# Programiralica.net
KiCad netlist of a schematic drawn in Altium Designer
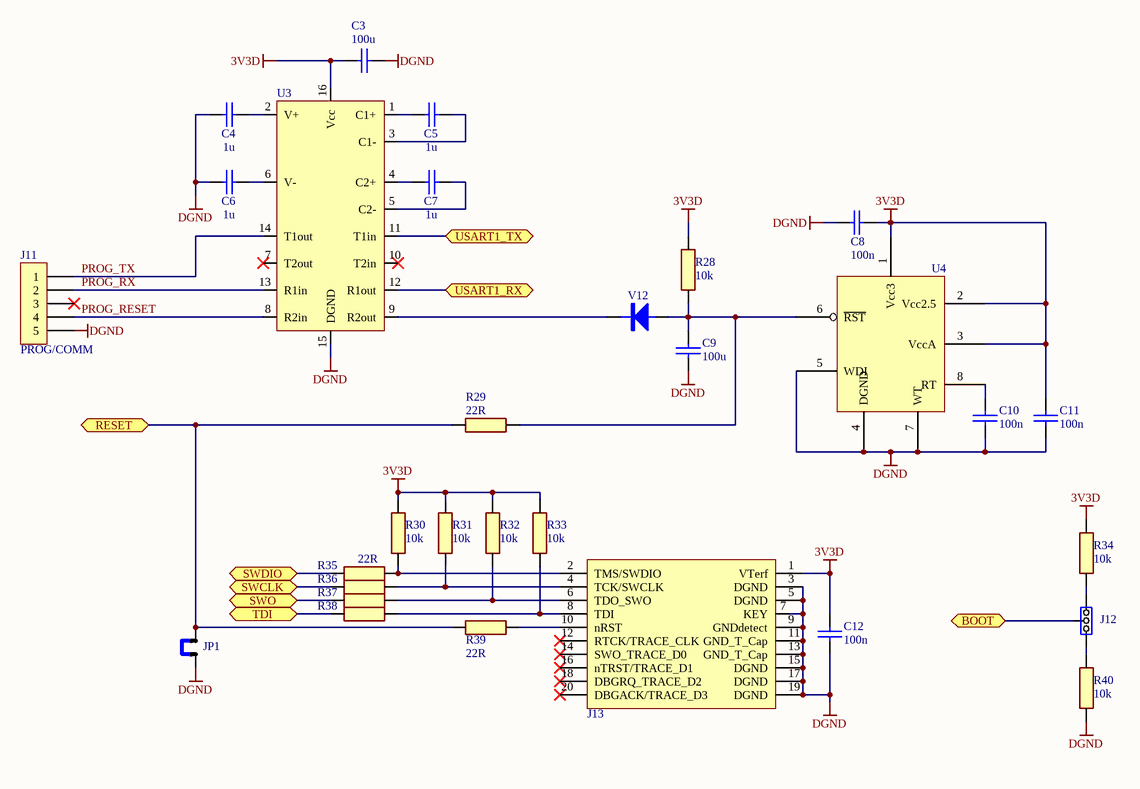
[diagram p0: Programiralica.SchDoc]

(export (version "E")
  (design (tool "Eeschema 10.0.6"))
  (components
    (comp (ref "C3")
      (value "100u")
      (footprint "CAP_0805_SMD")
      (description "0805")
      (libsource (lib "Moj_lib") (part "CAP"))
    )
    (comp (ref "C4")
      (value "1u")
      (footprint "CAP_0805_SMD")
      (description "0805")
      (libsource (lib "Moj_lib") (part "CAP"))
    )
    (comp (ref "C5")
      (value "1u")
      (footprint "CAP_0805_SMD")
      (description "0805")
      (libsource (lib "Moj_lib") (part "CAP"))
    )
    (comp (ref "C6")
      (value "1u")
      (footprint "CAP_0805_SMD")
      (description "0805")
      (libsource (lib "Moj_lib") (part "CAP"))
    )
    (comp (ref "C7")
      (value "1u")
      (footprint "CAP_0805_SMD")
      (description "0805")
      (libsource (lib "Moj_lib") (part "CAP"))
    )
    (comp (ref "C8")
      (value "100n")
      (footprint "CAP_0805_SMD")
      (description "0805")
      (libsource (lib "Moj_lib") (part "CAP"))
    )
    (comp (ref "C9")
      (value "100u")
      (footprint "CAP_0805_SMD")
      (description "0805")
      (libsource (lib "Moj_lib") (part "CAP"))
    )
    (comp (ref "C10")
      (value "100n")
      (footprint "CAP_0805_SMD")
      (description "0805")
      (libsource (lib "Moj_lib") (part "CAP"))
    )
    (comp (ref "C11")
      (value "100n")
      (footprint "CAP_0805_SMD")
      (description "0805")
      (libsource (lib "Moj_lib") (part "CAP"))
    )
    (comp (ref "C12")
      (value "100n")
      (footprint "CAP_0805_SMD")
      (description "0805")
      (libsource (lib "Moj_lib") (part "CAP"))
    )
    (comp (ref "J11")
      (value "PROG/COMM")
      (footprint "CON-SIP-5")
      (description "5 Pin connector")
      (libsource (lib "Moj_lib") (part "CON5"))
    )
    (comp (ref "J12")
      (value "JUMPER_3_POLE")
      (footprint "JUMPER_3_POLE")
      (description "3 Pole jumper")
      (libsource (lib "Moj_lib") (part "JUMPER_3_POLE"))
    )
    (comp (ref "J13")
      (value "JTAG-DEBUG-10x2")
      (footprint "JTAG-DEBUG-10x2-MOJ")
      (libsource (lib "Moj_lib") (part "CON-JTAG-10x2"))
    )
    (comp (ref "JP1")
      (value "JUMPER")
      (footprint "KRATKO-LEMNI")
      (description "Jumper")
      (libsource (lib "ShemaLibrary_IEL") (part "JUMPER"))
    )
    (comp (ref "R28")
      (value "10k")
      (footprint "RES_0805_SMD")
      (description "0805")
      (libsource (lib "") (part "RES_1"))
    )
    (comp (ref "R29")
      (value "22R")
      (footprint "RES_0805_SMD")
      (description "0805")
      (libsource (lib "") (part "RES_1"))
    )
    (comp (ref "R30")
      (value "10k")
      (footprint "RES_0805_SMD")
      (description "0805")
      (libsource (lib "Moj_lib") (part "RES"))
    )
    (comp (ref "R31")
      (value "10k")
      (footprint "RES_0805_SMD")
      (description "0805")
      (libsource (lib "Moj_lib") (part "RES"))
    )
    (comp (ref "R32")
      (value "10k")
      (footprint "RES_0805_SMD")
      (description "0805")
      (libsource (lib "Moj_lib") (part "RES"))
    )
    (comp (ref "R33")
      (value "10k")
      (footprint "RES_0805_SMD")
      (description "0805")
      (libsource (lib "Moj_lib") (part "RES"))
    )
    (comp (ref "R34")
      (value "10k")
      (footprint "RES_0805_SMD")
      (description "0805")
      (libsource (lib "Moj_lib") (part "RES"))
    )
    (comp (ref "R35")
      (value "22R")
      (footprint "RES_0805_SMD")
      (description "0805")
      (libsource (lib "") (part "RES_1"))
    )
    (comp (ref "R36")
      (value "22R")
      (footprint "RES_0805_SMD")
      (description "0805")
      (libsource (lib "") (part "RES_1"))
    )
    (comp (ref "R37")
      (value "22R")
      (footprint "RES_0805_SMD")
      (description "0805")
      (libsource (lib "") (part "RES_1"))
    )
    (comp (ref "R38")
      (value "22R")
      (footprint "RES_0805_SMD")
      (description "0805")
      (libsource (lib "") (part "RES_1"))
    )
    (comp (ref "R39")
      (value "22R")
      (footprint "RES_0805_SMD")
      (description "0805")
      (libsource (lib "") (part "RES_1"))
    )
    (comp (ref "R40")
      (value "10k")
      (footprint "RES_0805_SMD")
      (description "0805")
      (libsource (lib "Moj_lib") (part "RES"))
    )
    (comp (ref "U3")
      (value "MAX3232")
      (footprint "MAX3232")
      (description "RS232 chip")
      (libsource (lib "Moj_lib") (part "MAX3232"))
    )
    (comp (ref "U4") (value "LTC1726") (footprint "LTC1726") (libsource (lib "Moj_lib") (part "LTC1726")))
    (comp (ref "V12")
      (value "DIODE")
      (footprint "SOD-323F")
      (description "SMD diode")
      (libsource (lib "ShemaLibrary_IEL") (part "DIODE"))
    )
  )
  (nets
    (net (code "1") (name "/BOOT") (class "Default") (node (ref "J12") (pin "2") (pintype "passive")))
    (net (code "2") (name "/PROG_RESET") (class "Default")
      (node (ref "J11") (pin "4") (pinfunction "4_4") (pintype "passive"))
      (node (ref "U3") (pin "8") (pinfunction "R2in_8") (pintype "passive"))
    )
    (net (code "3") (name "/PROG_RX") (class "Default")
      (node (ref "J11") (pin "2") (pinfunction "2_2") (pintype "passive"))
      (node (ref "U3") (pin "13") (pinfunction "R1in_13") (pintype "passive"))
    )
    (net (code "4") (name "/PROG_TX") (class "Default")
      (node (ref "J11") (pin "1") (pinfunction "1_1") (pintype "passive"))
      (node (ref "U3") (pin "14") (pinfunction "T1out_14") (pintype "passive"))
    )
    (net (code "5") (name "/RESET") (class "Default")
      (node (ref "JP1") (pin "2") (pintype "passive"))
      (node (ref "R29") (pin "1") (pinfunction "1_1") (pintype "passive"))
      (node (ref "R39") (pin "1") (pinfunction "1_1") (pintype "passive"))
    )
    (net (code "6") (name "/SWCLK") (class "Default")
      (node (ref "R36") (pin "1") (pinfunction "1_1") (pintype "passive"))
    )
    (net (code "7") (name "/SWDIO") (class "Default")
      (node (ref "R35") (pin "1") (pinfunction "1_1") (pintype "passive"))
    )
    (net (code "8") (name "/SWO") (class "Default")
      (node (ref "R37") (pin "1") (pinfunction "1_1") (pintype "passive"))
    )
    (net (code "9") (name "/TDI") (class "Default")
      (node (ref "R38") (pin "1") (pinfunction "1_1") (pintype "passive"))
    )
    (net (code "10") (name "/USART1_RX") (class "Default")
      (node (ref "U3") (pin "12") (pinfunction "R1out_12") (pintype "passive"))
    )
    (net (code "11") (name "/USART1_TX") (class "Default")
      (node (ref "U3") (pin "11") (pinfunction "T1in_11") (pintype "passive"))
    )
    (net (code "12") (name "3V3D") (class "Default")
      (node (ref "C11") (pin "2") (pinfunction "2_2") (pintype "passive"))
      (node (ref "C12") (pin "2") (pinfunction "2_2") (pintype "passive"))
      (node (ref "C3") (pin "1") (pinfunction "1_1") (pintype "passive"))
      (node (ref "C8") (pin "1") (pinfunction "1_1") (pintype "passive"))
      (node (ref "J13") (pin "1") (pinfunction "VTerf_1") (pintype "passive"))
      (node (ref "R28") (pin "2") (pinfunction "2_2") (pintype "passive"))
      (node (ref "R30") (pin "2") (pinfunction "2_2") (pintype "passive"))
      (node (ref "R31") (pin "2") (pinfunction "2_2") (pintype "passive"))
      (node (ref "R32") (pin "2") (pinfunction "2_2") (pintype "passive"))
      (node (ref "R33") (pin "2") (pinfunction "2_2") (pintype "passive"))
      (node (ref "R34") (pin "2") (pinfunction "2_2") (pintype "passive"))
      (node (ref "U3") (pin "16") (pinfunction "Vcc_16") (pintype "passive"))
      (node (ref "U4") (pin "1") (pinfunction "Vcc3_1") (pintype "passive"))
      (node (ref "U4") (pin "2") (pinfunction "Vcc2.5_2") (pintype "passive"))
      (node (ref "U4") (pin "3") (pinfunction "VccA_3") (pintype "passive"))
    )
    (net (code "13") (name "DGND") (class "Default")
      (node (ref "C10") (pin "1") (pinfunction "1_1") (pintype "passive"))
      (node (ref "C11") (pin "1") (pinfunction "1_1") (pintype "passive"))
      (node (ref "C12") (pin "1") (pinfunction "1_1") (pintype "passive"))
      (node (ref "C3") (pin "2") (pinfunction "2_2") (pintype "passive"))
      (node (ref "C4") (pin "1") (pinfunction "1_1") (pintype "passive"))
      (node (ref "C6") (pin "1") (pinfunction "1_1") (pintype "passive"))
      (node (ref "C8") (pin "2") (pinfunction "2_2") (pintype "passive"))
      (node (ref "C9") (pin "1") (pinfunction "1_1") (pintype "passive"))
      (node (ref "J11") (pin "5") (pinfunction "5_5") (pintype "passive"))
      (node (ref "J13") (pin "11") (pinfunction "GND_T_Cap_11") (pintype "passive"))
      (node (ref "J13") (pin "13") (pinfunction "GND_T_Cap_13") (pintype "passive"))
      (node (ref "J13") (pin "15") (pinfunction "DGND_15") (pintype "passive"))
      (node (ref "J13") (pin "17") (pinfunction "DGND_17") (pintype "passive"))
      (node (ref "J13") (pin "19") (pinfunction "DGND_19") (pintype "passive"))
      (node (ref "J13") (pin "3") (pinfunction "DGND_3") (pintype "passive"))
      (node (ref "J13") (pin "5") (pinfunction "DGND_5") (pintype "passive"))
      (node (ref "J13") (pin "7") (pinfunction "KEY_7") (pintype "passive"))
      (node (ref "J13") (pin "9") (pinfunction "GNDdetect_9") (pintype "passive"))
      (node (ref "JP1") (pin "1") (pintype "passive"))
      (node (ref "R40") (pin "1") (pinfunction "1_1") (pintype "passive"))
      (node (ref "U3") (pin "15") (pinfunction "DGND_15") (pintype "passive"))
      (node (ref "U4") (pin "4") (pinfunction "DGND_4") (pintype "passive"))
      (node (ref "U4") (pin "5") (pinfunction "WDI_5") (pintype "passive"))
      (node (ref "U4") (pin "7") (pinfunction "WT_7") (pintype "passive"))
    )
    (net (code "14") (name "Net-(J12-Pad1)") (class "Default")
      (node (ref "J12") (pin "1") (pintype "passive"))
      (node (ref "R40") (pin "2") (pinfunction "2_2") (pintype "passive"))
    )
    (net (code "15") (name "Net-(J12-Pad3)") (class "Default")
      (node (ref "J12") (pin "3") (pintype "passive"))
      (node (ref "R34") (pin "1") (pinfunction "1_1") (pintype "passive"))
    )
    (net (code "16") (name "Net-(J13-TCK{slash}SWCLK)") (class "Default")
      (node (ref "J13") (pin "4") (pinfunction "TCK/SWCLK_4") (pintype "passive"))
      (node (ref "R31") (pin "1") (pinfunction "1_1") (pintype "passive"))
      (node (ref "R36") (pin "2") (pinfunction "2_2") (pintype "passive"))
    )
    (net (code "17") (name "Net-(J13-TDI)") (class "Default")
      (node (ref "J13") (pin "8") (pinfunction "TDI_8") (pintype "passive"))
      (node (ref "R33") (pin "1") (pinfunction "1_1") (pintype "passive"))
      (node (ref "R38") (pin "2") (pinfunction "2_2") (pintype "passive"))
    )
    (net (code "18") (name "Net-(J13-TDO_SWO)") (class "Default")
      (node (ref "J13") (pin "6") (pinfunction "TDO_SWO_6") (pintype "passive"))
      (node (ref "R32") (pin "1") (pinfunction "1_1") (pintype "passive"))
      (node (ref "R37") (pin "2") (pinfunction "2_2") (pintype "passive"))
    )
    (net (code "19") (name "Net-(J13-TMS{slash}SWDIO)") (class "Default")
      (node (ref "J13") (pin "2") (pinfunction "TMS/SWDIO_2") (pintype "passive"))
      (node (ref "R30") (pin "1") (pinfunction "1_1") (pintype "passive"))
      (node (ref "R35") (pin "2") (pinfunction "2_2") (pintype "passive"))
    )
    (net (code "20") (name "Net-(J13-nRST)") (class "Default")
      (node (ref "J13") (pin "10") (pinfunction "nRST_10") (pintype "passive"))
      (node (ref "R39") (pin "2") (pinfunction "2_2") (pintype "passive"))
    )
    (net (code "21") (name "Net-(U3-C1+)") (class "Default")
      (node (ref "C5") (pin "1") (pinfunction "1_1") (pintype "passive"))
      (node (ref "U3") (pin "1") (pinfunction "C1+_1") (pintype "passive"))
    )
    (net (code "22") (name "Net-(U3-C1-)") (class "Default")
      (node (ref "C5") (pin "2") (pinfunction "2_2") (pintype "passive"))
      (node (ref "U3") (pin "3") (pinfunction "C1-_3") (pintype "passive"))
    )
    (net (code "23") (name "Net-(U3-C2+)") (class "Default")
      (node (ref "C7") (pin "1") (pinfunction "1_1") (pintype "passive"))
      (node (ref "U3") (pin "4") (pinfunction "C2+_4") (pintype "passive"))
    )
    (net (code "24") (name "Net-(U3-C2-)") (class "Default")
      (node (ref "C7") (pin "2") (pinfunction "2_2") (pintype "passive"))
      (node (ref "U3") (pin "5") (pinfunction "C2-_5") (pintype "passive"))
    )
    (net (code "25") (name "Net-(U3-R2out)") (class "Default")
      (node (ref "U3") (pin "9") (pinfunction "R2out_9") (pintype "passive"))
      (node (ref "V12") (pin "2") (pinfunction "2_2") (pintype "passive"))
    )
    (net (code "26") (name "Net-(U3-V+)") (class "Default")
      (node (ref "C4") (pin "2") (pinfunction "2_2") (pintype "passive"))
      (node (ref "U3") (pin "2") (pinfunction "V+_2") (pintype "passive"))
    )
    (net (code "27") (name "Net-(U3-V-)") (class "Default")
      (node (ref "C6") (pin "2") (pinfunction "2_2") (pintype "passive"))
      (node (ref "U3") (pin "6") (pinfunction "V-_6") (pintype "passive"))
    )
    (net (code "28") (name "Net-(U4-RT)") (class "Default")
      (node (ref "C10") (pin "2") (pinfunction "2_2") (pintype "passive"))
      (node (ref "U4") (pin "8") (pinfunction "RT_8") (pintype "passive"))
    )
    (net (code "29") (name "Net-(U4-~{RST})") (class "Default")
      (node (ref "C9") (pin "2") (pinfunction "2_2") (pintype "passive"))
      (node (ref "R28") (pin "1") (pinfunction "1_1") (pintype "passive"))
      (node (ref "R29") (pin "2") (pinfunction "2_2") (pintype "passive"))
      (node (ref "U4") (pin "6") (pinfunction "~{RST}_6") (pintype "passive"))
      (node (ref "V12") (pin "1") (pinfunction "1_1") (pintype "passive"))
    )
    (net (code "30") (name "unconnected-(J11-Pad3)") (class "Default")
      (node (ref "J11") (pin "3") (pinfunction "3_3") (pintype "passive+no_connect"))
    )
    (net (code "31") (name "unconnected-(J13-DBGACK{slash}TRACE_D3-Pad20)") (class "Default")
      (node (ref "J13") (pin "20") (pinfunction "DBGACK/TRACE_D3_20") (pintype "passive+no_connect"))
    )
    (net (code "32") (name "unconnected-(J13-DBGRQ_TRACE_D2-Pad18)") (class "Default")
      (node (ref "J13") (pin "18") (pinfunction "DBGRQ_TRACE_D2_18") (pintype "passive+no_connect"))
    )
    (net (code "33") (name "unconnected-(J13-RTCK{slash}TRACE_CLK-Pad12)") (class "Default")
      (node (ref "J13") (pin "12") (pinfunction "RTCK/TRACE_CLK_12") (pintype "passive+no_connect"))
    )
    (net (code "34") (name "unconnected-(J13-SWO_TRACE_D0-Pad14)") (class "Default")
      (node (ref "J13") (pin "14") (pinfunction "SWO_TRACE_D0_14") (pintype "passive+no_connect"))
    )
    (net (code "35") (name "unconnected-(J13-nTRST{slash}TRACE_D1-Pad16)") (class "Default")
      (node (ref "J13") (pin "16") (pinfunction "nTRST/TRACE_D1_16") (pintype "passive+no_connect"))
    )
    (net (code "36") (name "unconnected-(U3-T2in-Pad10)") (class "Default")
      (node (ref "U3") (pin "10") (pinfunction "T2in_10") (pintype "passive+no_connect"))
    )
    (net (code "37") (name "unconnected-(U3-T2out-Pad7)") (class "Default")
      (node (ref "U3") (pin "7") (pinfunction "T2out_7") (pintype "passive+no_connect"))
    )
  )
)
